# MakespaceBadge-5x5.net
KiCad netlist of a schematic drawn in EAGLE
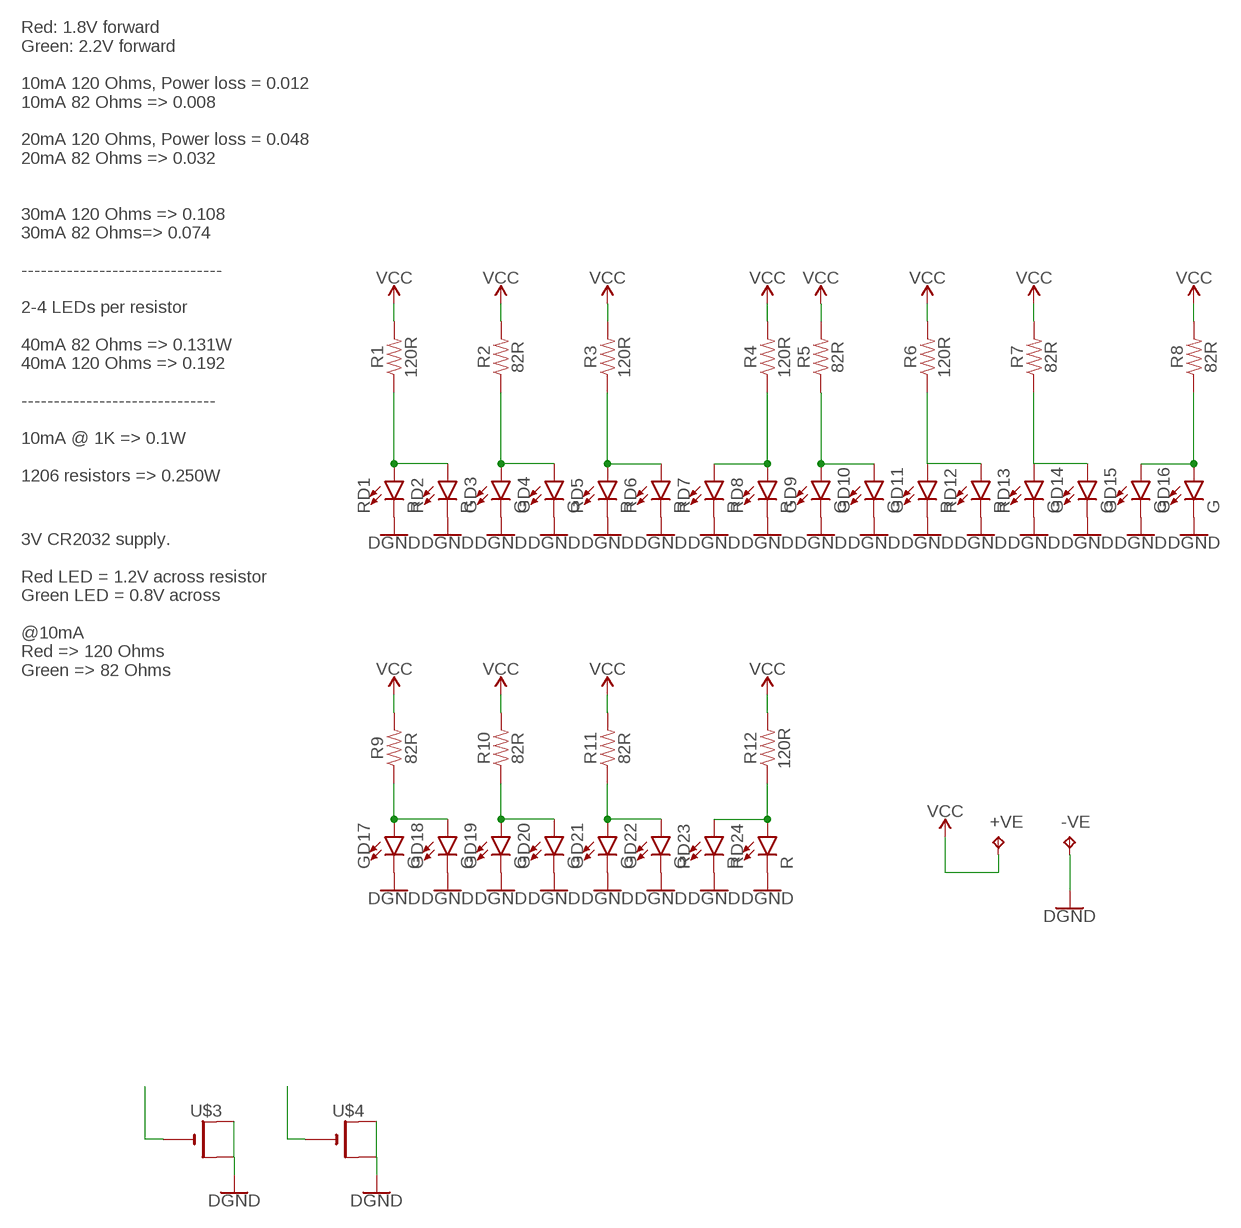
[diagram p0: schematic, sheet 1]

(export (version "E")
  (design (tool "Eeschema 10.0.6"))
  (components
    (comp (ref "+VE")
      (value "TPTP20SQ")
      (footprint "eagle-import:TP20SQ")
      (libsource (lib "eagle-import") (part "TPTP20SQ"))
    )
    (comp (ref "-VE")
      (value "TPTP20SQ")
      (footprint "eagle-import:TP20SQ")
      (libsource (lib "eagle-import") (part "TPTP20SQ"))
    )
    (comp (ref "GD3")
      (value "G")
      (footprint "eagle-import:LED_3MM")
      (libsource (lib "eagle-import") (part "LED3MM"))
    )
    (comp (ref "GD4")
      (value "G")
      (footprint "eagle-import:LED_3MM")
      (libsource (lib "eagle-import") (part "LED3MM"))
    )
    (comp (ref "GD9")
      (value "G")
      (footprint "eagle-import:LED_3MM")
      (libsource (lib "eagle-import") (part "LED3MM"))
    )
    (comp (ref "GD10")
      (value "G")
      (footprint "eagle-import:LED_3MM")
      (libsource (lib "eagle-import") (part "LED3MM"))
    )
    (comp (ref "GD11")
      (value "R")
      (footprint "eagle-import:LED_3MM")
      (libsource (lib "eagle-import") (part "LED3MM"))
    )
    (comp (ref "GD14")
      (value "G")
      (footprint "eagle-import:LED_3MM")
      (libsource (lib "eagle-import") (part "LED3MM"))
    )
    (comp (ref "GD15")
      (value "G")
      (footprint "eagle-import:LED_3MM")
      (libsource (lib "eagle-import") (part "LED3MM"))
    )
    (comp (ref "GD16")
      (value "G")
      (footprint "eagle-import:LED_3MM")
      (libsource (lib "eagle-import") (part "LED3MM"))
    )
    (comp (ref "GD17")
      (value "G")
      (footprint "eagle-import:LED_3MM")
      (libsource (lib "eagle-import") (part "LED3MM"))
    )
    (comp (ref "GD18")
      (value "G")
      (footprint "eagle-import:LED_3MM")
      (libsource (lib "eagle-import") (part "LED3MM"))
    )
    (comp (ref "GD19")
      (value "G")
      (footprint "eagle-import:LED_3MM")
      (libsource (lib "eagle-import") (part "LED3MM"))
    )
    (comp (ref "GD20")
      (value "G")
      (footprint "eagle-import:LED_3MM")
      (libsource (lib "eagle-import") (part "LED3MM"))
    )
    (comp (ref "GD21")
      (value "G")
      (footprint "eagle-import:LED_3MM")
      (libsource (lib "eagle-import") (part "LED3MM"))
    )
    (comp (ref "GD22")
      (value "G")
      (footprint "eagle-import:LED_3MM")
      (libsource (lib "eagle-import") (part "LED3MM"))
    )
    (comp (ref "R1")
      (value "120R")
      (footprint "eagle-import:1206")
      (libsource (lib "eagle-import") (part "RESISTOR1206"))
    )
    (comp (ref "R2")
      (value "82R")
      (footprint "eagle-import:1206")
      (libsource (lib "eagle-import") (part "RESISTOR1206"))
    )
    (comp (ref "R3")
      (value "120R")
      (footprint "eagle-import:1206")
      (libsource (lib "eagle-import") (part "RESISTOR1206"))
    )
    (comp (ref "R4")
      (value "120R")
      (footprint "eagle-import:1206")
      (libsource (lib "eagle-import") (part "RESISTOR1206"))
    )
    (comp (ref "R5")
      (value "82R")
      (footprint "eagle-import:1206")
      (libsource (lib "eagle-import") (part "RESISTOR1206"))
    )
    (comp (ref "R6")
      (value "120R")
      (footprint "eagle-import:1206")
      (libsource (lib "eagle-import") (part "RESISTOR1206"))
    )
    (comp (ref "R7")
      (value "82R")
      (footprint "eagle-import:1206")
      (libsource (lib "eagle-import") (part "RESISTOR1206"))
    )
    (comp (ref "R8")
      (value "82R")
      (footprint "eagle-import:1206")
      (libsource (lib "eagle-import") (part "RESISTOR1206"))
    )
    (comp (ref "R9")
      (value "82R")
      (footprint "eagle-import:1206")
      (libsource (lib "eagle-import") (part "RESISTOR1206"))
    )
    (comp (ref "R10")
      (value "82R")
      (footprint "eagle-import:1206")
      (libsource (lib "eagle-import") (part "RESISTOR1206"))
    )
    (comp (ref "R11")
      (value "82R")
      (footprint "eagle-import:1206")
      (libsource (lib "eagle-import") (part "RESISTOR1206"))
    )
    (comp (ref "R12")
      (value "120R")
      (footprint "eagle-import:1206")
      (libsource (lib "eagle-import") (part "RESISTOR1206"))
    )
    (comp (ref "RD1")
      (value "R")
      (footprint "eagle-import:LED_3MM")
      (libsource (lib "eagle-import") (part "LED3MM"))
    )
    (comp (ref "RD2")
      (value "R")
      (footprint "eagle-import:LED_3MM")
      (libsource (lib "eagle-import") (part "LED3MM"))
    )
    (comp (ref "RD5")
      (value "R")
      (footprint "eagle-import:LED_3MM")
      (libsource (lib "eagle-import") (part "LED3MM"))
    )
    (comp (ref "RD6")
      (value "R")
      (footprint "eagle-import:LED_3MM")
      (libsource (lib "eagle-import") (part "LED3MM"))
    )
    (comp (ref "RD7")
      (value "R")
      (footprint "eagle-import:LED_3MM")
      (libsource (lib "eagle-import") (part "LED3MM"))
    )
    (comp (ref "RD8")
      (value "R")
      (footprint "eagle-import:LED_3MM")
      (libsource (lib "eagle-import") (part "LED3MM"))
    )
    (comp (ref "RD12")
      (value "R")
      (footprint "eagle-import:LED_3MM")
      (libsource (lib "eagle-import") (part "LED3MM"))
    )
    (comp (ref "RD13")
      (value "G")
      (footprint "eagle-import:LED_3MM")
      (libsource (lib "eagle-import") (part "LED3MM"))
    )
    (comp (ref "RD23")
      (value "R")
      (footprint "eagle-import:LED_3MM")
      (libsource (lib "eagle-import") (part "LED3MM"))
    )
    (comp (ref "RD24")
      (value "R")
      (footprint "eagle-import:LED_3MM")
      (libsource (lib "eagle-import") (part "LED3MM"))
    )
    (comp (ref "U$3")
      (value "CR1220SMT")
      (footprint "eagle-import:CR1220-SMD")
      (libsource (lib "eagle-import") (part "CR1220SMT"))
    )
    (comp (ref "U$4")
      (value "CR1220SMT")
      (footprint "eagle-import:CR1220-SMD")
      (libsource (lib "eagle-import") (part "CR1220SMT"))
    )
  )
  (nets
    (net (code "1") (name "DGND") (class "Default")
      (node (ref "-VE") (pin "TP") (pinfunction "TP_TP") (pintype "input"))
      (node (ref "GD10") (pin "K") (pinfunction "C_K") (pintype "passive"))
      (node (ref "GD11") (pin "K") (pinfunction "C_K") (pintype "passive"))
      (node (ref "GD14") (pin "K") (pinfunction "C_K") (pintype "passive"))
      (node (ref "GD15") (pin "K") (pinfunction "C_K") (pintype "passive"))
      (node (ref "GD16") (pin "K") (pinfunction "C_K") (pintype "passive"))
      (node (ref "GD17") (pin "K") (pinfunction "C_K") (pintype "passive"))
      (node (ref "GD18") (pin "K") (pinfunction "C_K") (pintype "passive"))
      (node (ref "GD19") (pin "K") (pinfunction "C_K") (pintype "passive"))
      (node (ref "GD20") (pin "K") (pinfunction "C_K") (pintype "passive"))
      (node (ref "GD21") (pin "K") (pinfunction "C_K") (pintype "passive"))
      (node (ref "GD22") (pin "K") (pinfunction "C_K") (pintype "passive"))
      (node (ref "GD3") (pin "K") (pinfunction "C_K") (pintype "passive"))
      (node (ref "GD4") (pin "K") (pinfunction "C_K") (pintype "passive"))
      (node (ref "GD9") (pin "K") (pinfunction "C_K") (pintype "passive"))
      (node (ref "RD1") (pin "K") (pinfunction "C_K") (pintype "passive"))
      (node (ref "RD12") (pin "K") (pinfunction "C_K") (pintype "passive"))
      (node (ref "RD13") (pin "K") (pinfunction "C_K") (pintype "passive"))
      (node (ref "RD2") (pin "K") (pinfunction "C_K") (pintype "passive"))
      (node (ref "RD23") (pin "K") (pinfunction "C_K") (pintype "passive"))
      (node (ref "RD24") (pin "K") (pinfunction "C_K") (pintype "passive"))
      (node (ref "RD5") (pin "K") (pinfunction "C_K") (pintype "passive"))
      (node (ref "RD6") (pin "K") (pinfunction "C_K") (pintype "passive"))
      (node (ref "RD7") (pin "K") (pinfunction "C_K") (pintype "passive"))
      (node (ref "RD8") (pin "K") (pinfunction "C_K") (pintype "passive"))
      (node (ref "U$3") (pin "+$1") (pinfunction "+_+$1") (pintype "passive"))
      (node (ref "U$3") (pin "+$2") (pinfunction "+1_+$2") (pintype "passive"))
      (node (ref "U$4") (pin "+$1") (pinfunction "+_+$1") (pintype "passive"))
      (node (ref "U$4") (pin "+$2") (pinfunction "+1_+$2") (pintype "passive"))
    )
    (net (code "2") (name "Net-(GD3-PadA)") (class "Default")
      (node (ref "GD3") (pin "A") (pinfunction "A_A") (pintype "passive"))
      (node (ref "GD4") (pin "A") (pinfunction "A_A") (pintype "passive"))
      (node (ref "R2") (pin "1") (pinfunction "1_1") (pintype "passive"))
    )
    (net (code "3") (name "Net-(GD10-PadA)") (class "Default")
      (node (ref "GD10") (pin "A") (pinfunction "A_A") (pintype "passive"))
      (node (ref "GD9") (pin "A") (pinfunction "A_A") (pintype "passive"))
      (node (ref "R5") (pin "1") (pinfunction "1_1") (pintype "passive"))
    )
    (net (code "4") (name "Net-(GD11-PadA)") (class "Default")
      (node (ref "GD11") (pin "A") (pinfunction "A_A") (pintype "passive"))
      (node (ref "R6") (pin "1") (pinfunction "1_1") (pintype "passive"))
      (node (ref "RD12") (pin "A") (pinfunction "A_A") (pintype "passive"))
    )
    (net (code "5") (name "Net-(GD14-PadA)") (class "Default")
      (node (ref "GD14") (pin "A") (pinfunction "A_A") (pintype "passive"))
      (node (ref "R7") (pin "1") (pinfunction "1_1") (pintype "passive"))
      (node (ref "RD13") (pin "A") (pinfunction "A_A") (pintype "passive"))
    )
    (net (code "6") (name "Net-(GD15-PadA)") (class "Default")
      (node (ref "GD15") (pin "A") (pinfunction "A_A") (pintype "passive"))
      (node (ref "GD16") (pin "A") (pinfunction "A_A") (pintype "passive"))
      (node (ref "R8") (pin "1") (pinfunction "1_1") (pintype "passive"))
    )
    (net (code "7") (name "Net-(GD17-PadA)") (class "Default")
      (node (ref "GD17") (pin "A") (pinfunction "A_A") (pintype "passive"))
      (node (ref "GD18") (pin "A") (pinfunction "A_A") (pintype "passive"))
      (node (ref "R9") (pin "1") (pinfunction "1_1") (pintype "passive"))
    )
    (net (code "8") (name "Net-(GD19-PadA)") (class "Default")
      (node (ref "GD19") (pin "A") (pinfunction "A_A") (pintype "passive"))
      (node (ref "GD20") (pin "A") (pinfunction "A_A") (pintype "passive"))
      (node (ref "R10") (pin "1") (pinfunction "1_1") (pintype "passive"))
    )
    (net (code "9") (name "Net-(GD21-PadA)") (class "Default")
      (node (ref "GD21") (pin "A") (pinfunction "A_A") (pintype "passive"))
      (node (ref "GD22") (pin "A") (pinfunction "A_A") (pintype "passive"))
      (node (ref "R11") (pin "1") (pinfunction "1_1") (pintype "passive"))
    )
    (net (code "10") (name "Net-(R1-Pad1)") (class "Default")
      (node (ref "R1") (pin "1") (pinfunction "1_1") (pintype "passive"))
      (node (ref "RD1") (pin "A") (pinfunction "A_A") (pintype "passive"))
      (node (ref "RD2") (pin "A") (pinfunction "A_A") (pintype "passive"))
    )
    (net (code "11") (name "Net-(R3-Pad1)") (class "Default")
      (node (ref "R3") (pin "1") (pinfunction "1_1") (pintype "passive"))
      (node (ref "RD5") (pin "A") (pinfunction "A_A") (pintype "passive"))
      (node (ref "RD6") (pin "A") (pinfunction "A_A") (pintype "passive"))
    )
    (net (code "12") (name "Net-(R4-Pad1)") (class "Default")
      (node (ref "R4") (pin "1") (pinfunction "1_1") (pintype "passive"))
      (node (ref "RD7") (pin "A") (pinfunction "A_A") (pintype "passive"))
      (node (ref "RD8") (pin "A") (pinfunction "A_A") (pintype "passive"))
    )
    (net (code "13") (name "Net-(R12-Pad1)") (class "Default")
      (node (ref "R12") (pin "1") (pinfunction "1_1") (pintype "passive"))
      (node (ref "RD23") (pin "A") (pinfunction "A_A") (pintype "passive"))
      (node (ref "RD24") (pin "A") (pinfunction "A_A") (pintype "passive"))
    )
    (net (code "14") (name "VCC") (class "Default")
      (node (ref "+VE") (pin "TP") (pinfunction "TP_TP") (pintype "input"))
      (node (ref "R1") (pin "2") (pinfunction "2_2") (pintype "passive"))
      (node (ref "R10") (pin "2") (pinfunction "2_2") (pintype "passive"))
      (node (ref "R11") (pin "2") (pinfunction "2_2") (pintype "passive"))
      (node (ref "R12") (pin "2") (pinfunction "2_2") (pintype "passive"))
      (node (ref "R2") (pin "2") (pinfunction "2_2") (pintype "passive"))
      (node (ref "R3") (pin "2") (pinfunction "2_2") (pintype "passive"))
      (node (ref "R4") (pin "2") (pinfunction "2_2") (pintype "passive"))
      (node (ref "R5") (pin "2") (pinfunction "2_2") (pintype "passive"))
      (node (ref "R6") (pin "2") (pinfunction "2_2") (pintype "passive"))
      (node (ref "R7") (pin "2") (pinfunction "2_2") (pintype "passive"))
      (node (ref "R8") (pin "2") (pinfunction "2_2") (pintype "passive"))
      (node (ref "R9") (pin "2") (pinfunction "2_2") (pintype "passive"))
    )
    (net (code "15") (name "unconnected-(U$3-Pad-)") (class "Default")
      (node (ref "U$3") (pin "-") (pinfunction "-_-") (pintype "passive"))
    )
    (net (code "16") (name "unconnected-(U$4-Pad-)") (class "Default")
      (node (ref "U$4") (pin "-") (pinfunction "-_-") (pintype "passive"))
    )
  )
)
